# Quarfinder.net
KiCad netlist of a schematic drawn in EAGLE
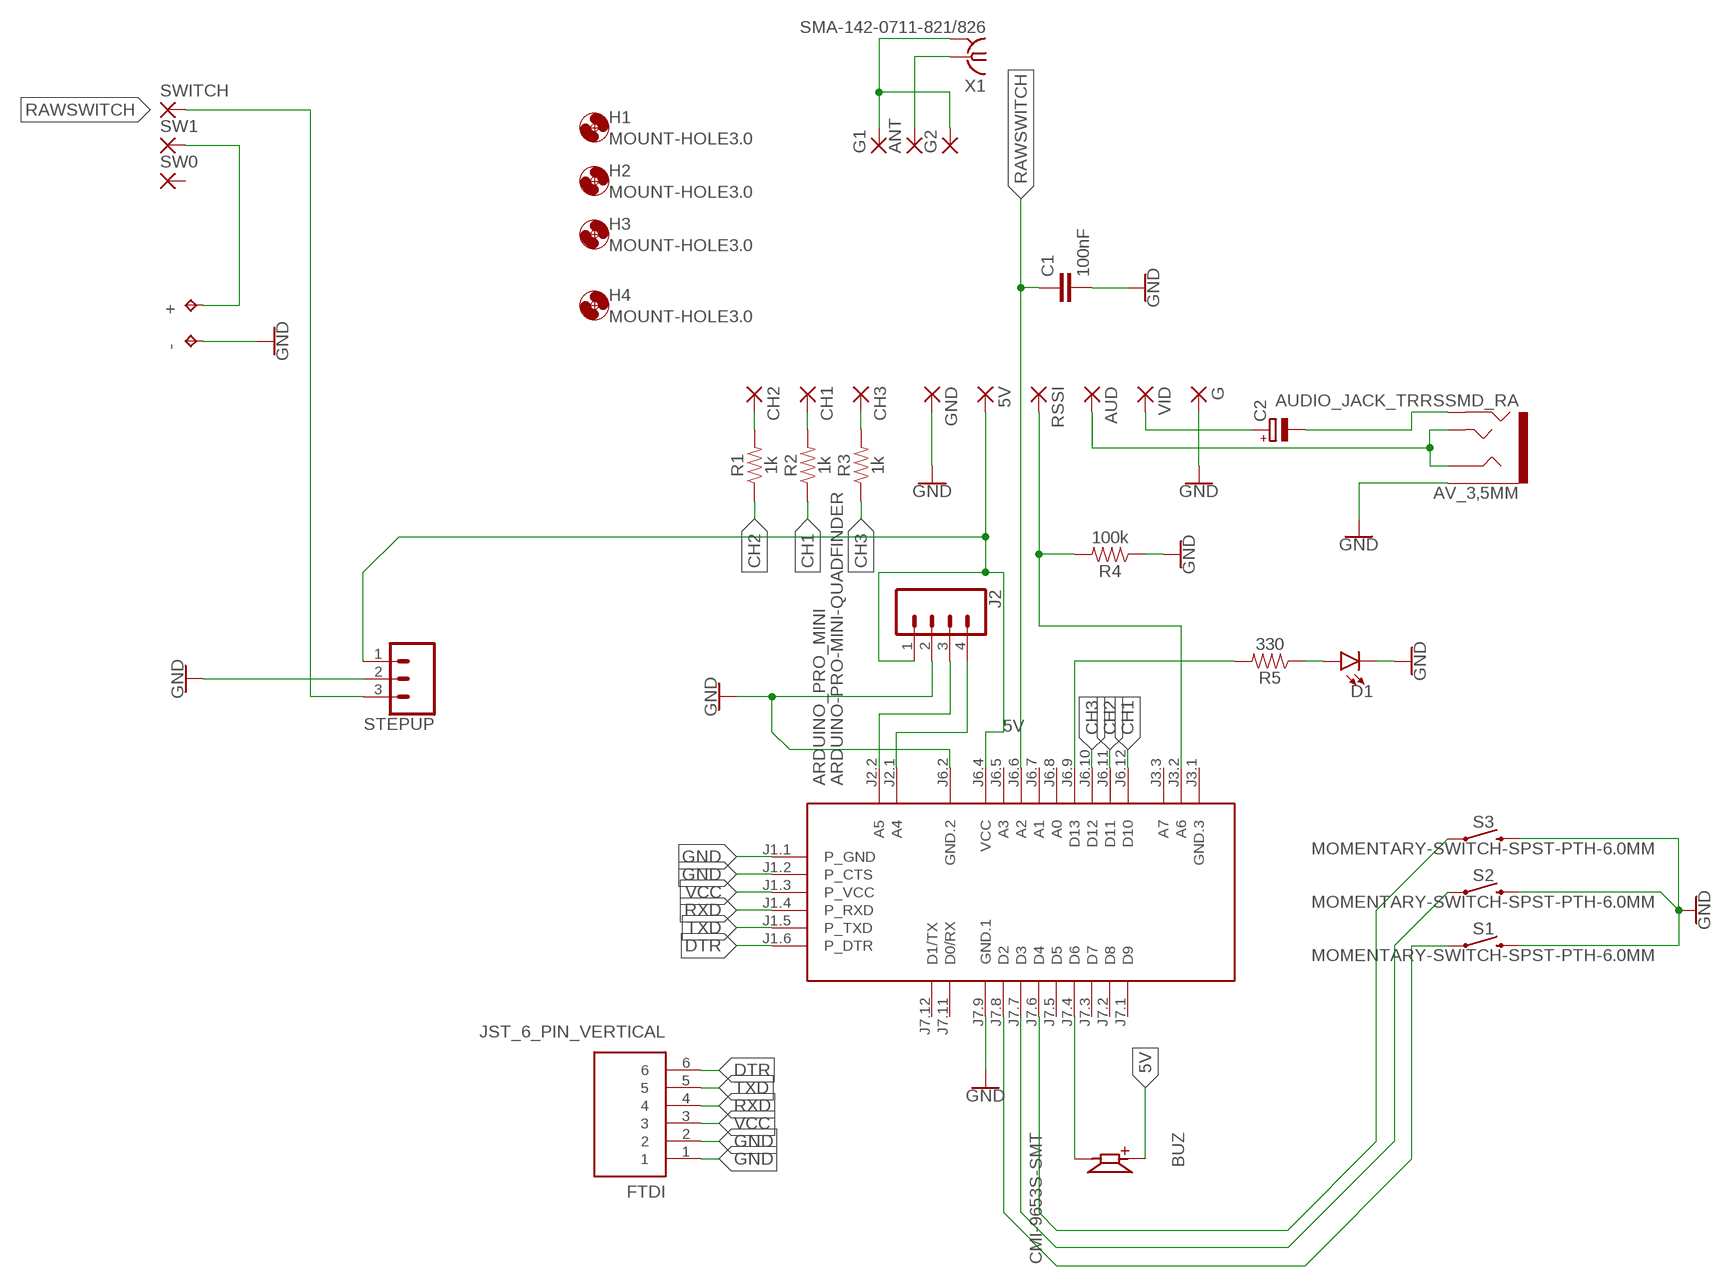
[diagram p0: schematic, sheet 1]

(export (version "E")
  (design (tool "Eeschema 10.0.6"))
  (components
    (comp (ref "+")
      (value "TPTP20R")
      (footprint "eagle-import:TP20R")
      (libsource (lib "eagle-import") (part "TPTP20R"))
    )
    (comp (ref "-")
      (value "TPTP20R")
      (footprint "eagle-import:TP20R")
      (libsource (lib "eagle-import") (part "TPTP20R"))
    )
    (comp (ref "5V")
      (value "SMD2")
      (footprint "eagle-import:SMD1,27-2,54")
      (libsource (lib "eagle-import") (part "SMD2"))
    )
    (comp (ref "ANT")
      (value "SMD2")
      (footprint "eagle-import:SMD1,27-2,54")
      (libsource (lib "eagle-import") (part "SMD2"))
    )
    (comp (ref "ARDUINO_PRO_MINI")
      (value "ARDUINO-PRO-MINI-QUADFINDER")
      (footprint "eagle-import:ARDUINO-PRO-MINI")
      (libsource (lib "eagle-import") (part "ARDUINO-PRO-MINI-QUADFINDER"))
    )
    (comp (ref "AUD")
      (value "SMD2")
      (footprint "eagle-import:SMD1,27-2,54")
      (libsource (lib "eagle-import") (part "SMD2"))
    )
    (comp (ref "AV_3,5MM")
      (value "AUDIO_JACK_TRRSSMD_RA")
      (footprint "eagle-import:AUDIO_JACK_3.5MM_TRRS_SMD_RA")
      (libsource (lib "eagle-import") (part "AUDIO_JACK_TRRSSMD_RA"))
    )
    (comp (ref "BUZ")
      (value "CMI-9653S-SMT")
      (footprint "eagle-import:CUI_CMI-9653S-SMT")
      (fields (field (name "MF") "CUI Inc.") (field (name "MP") "CMI-9653S-SMT-TR"))
      (libsource (lib "eagle-import") (part "CMI-9653S-SMT"))
    )
    (comp (ref "C1")
      (value "100nF")
      (footprint "eagle-import:0603")
      (libsource (lib "eagle-import") (part "1.0UF-0603-16V-10%"))
    )
    (comp (ref "C2")
      (value "CPOL-EUD/7343-31R")
      (footprint "eagle-import:D_7343-31R")
      (libsource (lib "eagle-import") (part "CPOL-EUD/7343-31R"))
    )
    (comp (ref "CH1")
      (value "SMD2")
      (footprint "eagle-import:SMD1,27-2,54")
      (libsource (lib "eagle-import") (part "SMD2"))
    )
    (comp (ref "CH2")
      (value "SMD2")
      (footprint "eagle-import:SMD1,27-2,54")
      (libsource (lib "eagle-import") (part "SMD2"))
    )
    (comp (ref "CH3")
      (value "SMD2")
      (footprint "eagle-import:SMD1,27-2,54")
      (libsource (lib "eagle-import") (part "SMD2"))
    )
    (comp (ref "D1")
      (value "LED3MM")
      (footprint "eagle-import:LED_3MM")
      (libsource (lib "eagle-import") (part "LED3MM"))
    )
    (comp (ref "FTDI")
      (value "JST_6_PIN_VERTICAL")
      (footprint "eagle-import:JST-6-SMD-VERT-1.0MM")
      (libsource (lib "eagle-import") (part "JST_6_PIN_VERTICAL"))
    )
    (comp (ref "G")
      (value "SMD2")
      (footprint "eagle-import:SMD1,27-2,54")
      (libsource (lib "eagle-import") (part "SMD2"))
    )
    (comp (ref "G1")
      (value "SMD2")
      (footprint "eagle-import:SMD1,27-2,54")
      (libsource (lib "eagle-import") (part "SMD2"))
    )
    (comp (ref "G2")
      (value "SMD2")
      (footprint "eagle-import:SMD1,27-2,54")
      (libsource (lib "eagle-import") (part "SMD2"))
    )
    (comp (ref "GND")
      (value "SMD2")
      (footprint "eagle-import:SMD1,27-2,54")
      (libsource (lib "eagle-import") (part "SMD2"))
    )
    (comp (ref "H1")
      (value "MOUNT-HOLE3.0")
      (footprint "eagle-import:3,0")
      (libsource (lib "eagle-import") (part "MOUNT-HOLE3.0"))
    )
    (comp (ref "H2")
      (value "MOUNT-HOLE3.0")
      (footprint "eagle-import:3,0")
      (libsource (lib "eagle-import") (part "MOUNT-HOLE3.0"))
    )
    (comp (ref "H3")
      (value "MOUNT-HOLE3.0")
      (footprint "eagle-import:3,0")
      (libsource (lib "eagle-import") (part "MOUNT-HOLE3.0"))
    )
    (comp (ref "H4")
      (value "MOUNT-HOLE3.0")
      (footprint "eagle-import:3,0")
      (libsource (lib "eagle-import") (part "MOUNT-HOLE3.0"))
    )
    (comp (ref "J2")
      (value "CONN_04")
      (footprint "eagle-import:1X04")
      (libsource (lib "eagle-import") (part "CONN_04"))
    )
    (comp (ref "R1")
      (value "1k")
      (footprint "eagle-import:0603")
      (libsource (lib "eagle-import") (part "1KOHM-0603-1/10W-1%"))
    )
    (comp (ref "R2")
      (value "1k")
      (footprint "eagle-import:0603")
      (libsource (lib "eagle-import") (part "1KOHM-0603-1/10W-1%"))
    )
    (comp (ref "R3")
      (value "1k")
      (footprint "eagle-import:0603")
      (libsource (lib "eagle-import") (part "1KOHM-0603-1/10W-1%"))
    )
    (comp (ref "R4")
      (value "100k")
      (footprint "eagle-import:0603")
      (libsource (lib "eagle-import") (part "1KOHM-0603-1/10W-1%"))
    )
    (comp (ref "R5")
      (value "330")
      (footprint "eagle-import:0603")
      (libsource (lib "eagle-import") (part "1KOHM-0603-1/10W-1%"))
    )
    (comp (ref "RSSI")
      (value "SMD2")
      (footprint "eagle-import:SMD1,27-2,54")
      (libsource (lib "eagle-import") (part "SMD2"))
    )
    (comp (ref "S1")
      (value "MOMENTARY-SWITCH-SPST-PTH-6.0MM")
      (footprint "eagle-import:TACTILE_SWITCH_PTH_6.0MM")
      (libsource (lib "eagle-import") (part "MOMENTARY-SWITCH-SPST-PTH-6.0MM"))
    )
    (comp (ref "S2")
      (value "MOMENTARY-SWITCH-SPST-PTH-6.0MM")
      (footprint "eagle-import:TACTILE_SWITCH_PTH_6.0MM")
      (libsource (lib "eagle-import") (part "MOMENTARY-SWITCH-SPST-PTH-6.0MM"))
    )
    (comp (ref "S3")
      (value "MOMENTARY-SWITCH-SPST-PTH-6.0MM")
      (footprint "eagle-import:TACTILE_SWITCH_PTH_6.0MM")
      (libsource (lib "eagle-import") (part "MOMENTARY-SWITCH-SPST-PTH-6.0MM"))
    )
    (comp (ref "STEPUP")
      (value "CONN_03")
      (footprint "eagle-import:1X03")
      (libsource (lib "eagle-import") (part "CONN_03"))
    )
    (comp (ref "SW0")
      (value "SMD2")
      (footprint "eagle-import:SMD1,27-2,54")
      (libsource (lib "eagle-import") (part "SMD2"))
    )
    (comp (ref "SW1")
      (value "SMD2")
      (footprint "eagle-import:SMD1,27-2,54")
      (libsource (lib "eagle-import") (part "SMD2"))
    )
    (comp (ref "SWITCH")
      (value "SMD2")
      (footprint "eagle-import:SMD1,27-2,54")
      (libsource (lib "eagle-import") (part "SMD2"))
    )
    (comp (ref "VID")
      (value "SMD2")
      (footprint "eagle-import:SMD1,27-2,54")
      (libsource (lib "eagle-import") (part "SMD2"))
    )
    (comp (ref "X1")
      (value "SMA-142-0711-821/826")
      (footprint "eagle-import:J502-ND-142-0711-821_826")
      (fields (field (name "MF") "JOHNSON COMPONENTS") (field (name "MPN") "142-0711-821"))
      (libsource (lib "eagle-import") (part "SMA-142-0711-821/826"))
    )
  )
  (nets
    (net (code "1") (name "5V") (class "Default")
      (node (ref "5V") (pin "1") (pinfunction "P_1") (pintype "passive"))
      (node (ref "ARDUINO_PRO_MINI") (pin "J6.4") (pinfunction "VCC_J6.4") (pintype "power_in"))
      (node (ref "BUZ") (pin "P") (pinfunction "P_P") (pintype "passive"))
      (node (ref "J2") (pin "1") (pinfunction "1_1") (pintype "passive"))
      (node (ref "STEPUP") (pin "1") (pinfunction "1_1") (pintype "passive"))
    )
    (net (code "2") (name "CH1") (class "Default")
      (node (ref "ARDUINO_PRO_MINI") (pin "J6.12") (pinfunction "D10_J6.12") (pintype "bidirectional"))
      (node (ref "R2") (pin "1") (pinfunction "1_1") (pintype "passive"))
    )
    (net (code "3") (name "CH2") (class "Default")
      (node (ref "ARDUINO_PRO_MINI") (pin "J6.11") (pinfunction "D11_J6.11") (pintype "bidirectional"))
      (node (ref "R1") (pin "1") (pinfunction "1_1") (pintype "passive"))
    )
    (net (code "4") (name "CH3") (class "Default")
      (node (ref "ARDUINO_PRO_MINI") (pin "J6.10") (pinfunction "D12_J6.10") (pintype "bidirectional"))
      (node (ref "R3") (pin "1") (pinfunction "1_1") (pintype "passive"))
    )
    (net (code "5") (name "DTR") (class "Default")
      (node (ref "ARDUINO_PRO_MINI") (pin "J1.6") (pinfunction "P_DTR_J1.6") (pintype "bidirectional"))
      (node (ref "FTDI") (pin "6") (pinfunction "6_6") (pintype "bidirectional"))
    )
    (net (code "6") (name "GND") (class "Default")
      (node (ref "-") (pin "TP") (pinfunction "TP_TP") (pintype "input"))
      (node (ref "ARDUINO_PRO_MINI") (pin "J1.1") (pinfunction "P_GND_J1.1") (pintype "bidirectional"))
      (node (ref "ARDUINO_PRO_MINI") (pin "J1.2") (pinfunction "P_CTS_J1.2") (pintype "bidirectional"))
      (node (ref "ARDUINO_PRO_MINI") (pin "J6.2") (pinfunction "GND.2_J6.2") (pintype "power_in"))
      (node (ref "ARDUINO_PRO_MINI") (pin "J7.9") (pinfunction "GND.1_J7.9") (pintype "power_in"))
      (node (ref "AV_3,5MM") (pin "EARTH") (pinfunction "EARTH_EARTH") (pintype "bidirectional"))
      (node (ref "C1") (pin "2") (pinfunction "2_2") (pintype "passive"))
      (node (ref "D1") (pin "K") (pinfunction "C_K") (pintype "passive"))
      (node (ref "FTDI") (pin "1") (pinfunction "1_1") (pintype "bidirectional"))
      (node (ref "FTDI") (pin "2") (pinfunction "2_2") (pintype "bidirectional"))
      (node (ref "G") (pin "1") (pinfunction "P_1") (pintype "passive"))
      (node (ref "G1") (pin "1") (pinfunction "P_1") (pintype "passive"))
      (node (ref "G2") (pin "1") (pinfunction "P_1") (pintype "passive"))
      (node (ref "GND") (pin "1") (pinfunction "P_1") (pintype "passive"))
      (node (ref "J2") (pin "2") (pinfunction "2_2") (pintype "passive"))
      (node (ref "R4") (pin "1") (pinfunction "1_1") (pintype "passive"))
      (node (ref "S1") (pin "3") (pinfunction "2_3") (pintype "passive"))
      (node (ref "S2") (pin "3") (pinfunction "2_3") (pintype "passive"))
      (node (ref "S3") (pin "3") (pinfunction "2_3") (pintype "passive"))
      (node (ref "STEPUP") (pin "2") (pinfunction "2_2") (pintype "passive"))
      (node (ref "X1") (pin "G@1") (pinfunction "2_G@1") (pintype "passive"))
      (node (ref "X1") (pin "G@2") (pinfunction "2_G@2") (pintype "passive"))
      (node (ref "X1") (pin "G@3") (pinfunction "2_G@3") (pintype "passive"))
      (node (ref "X1") (pin "G@4") (pinfunction "2_G@4") (pintype "passive"))
    )
    (net (code "7") (name "Net-(ANT-P)") (class "Default")
      (node (ref "ANT") (pin "1") (pinfunction "P_1") (pintype "passive"))
      (node (ref "X1") (pin "1") (pinfunction "1_1") (pintype "passive"))
    )
    (net (code "8") (name "Net-(ARDUINO_PRO_MINI-A4)") (class "Default")
      (node (ref "ARDUINO_PRO_MINI") (pin "J2.1") (pinfunction "A4_J2.1") (pintype "bidirectional"))
      (node (ref "J2") (pin "4") (pinfunction "4_4") (pintype "passive"))
    )
    (net (code "9") (name "Net-(ARDUINO_PRO_MINI-A5)") (class "Default")
      (node (ref "ARDUINO_PRO_MINI") (pin "J2.2") (pinfunction "A5_J2.2") (pintype "bidirectional"))
      (node (ref "J2") (pin "3") (pinfunction "3_3") (pintype "passive"))
    )
    (net (code "10") (name "Net-(ARDUINO_PRO_MINI-A6)") (class "Default")
      (node (ref "ARDUINO_PRO_MINI") (pin "J3.2") (pinfunction "A6_J3.2") (pintype "bidirectional"))
      (node (ref "R4") (pin "2") (pinfunction "2_2") (pintype "passive"))
      (node (ref "RSSI") (pin "1") (pinfunction "P_1") (pintype "passive"))
    )
    (net (code "11") (name "Net-(ARDUINO_PRO_MINI-D2)") (class "Default")
      (node (ref "ARDUINO_PRO_MINI") (pin "J7.8") (pinfunction "D2_J7.8") (pintype "bidirectional"))
      (node (ref "S1") (pin "1") (pinfunction "1_1") (pintype "passive"))
    )
    (net (code "12") (name "Net-(ARDUINO_PRO_MINI-D3)") (class "Default")
      (node (ref "ARDUINO_PRO_MINI") (pin "J7.7") (pinfunction "D3_J7.7") (pintype "bidirectional"))
      (node (ref "S2") (pin "1") (pinfunction "1_1") (pintype "passive"))
    )
    (net (code "13") (name "Net-(ARDUINO_PRO_MINI-D4)") (class "Default")
      (node (ref "ARDUINO_PRO_MINI") (pin "J7.6") (pinfunction "D4_J7.6") (pintype "bidirectional"))
      (node (ref "S3") (pin "1") (pinfunction "1_1") (pintype "passive"))
    )
    (net (code "14") (name "Net-(ARDUINO_PRO_MINI-D6)") (class "Default")
      (node (ref "ARDUINO_PRO_MINI") (pin "J7.4") (pinfunction "D6_J7.4") (pintype "bidirectional"))
      (node (ref "BUZ") (pin "N") (pinfunction "N_N") (pintype "passive"))
    )
    (net (code "15") (name "Net-(ARDUINO_PRO_MINI-D13)") (class "Default")
      (node (ref "ARDUINO_PRO_MINI") (pin "J6.9") (pinfunction "D13_J6.9") (pintype "bidirectional"))
      (node (ref "R5") (pin "2") (pinfunction "2_2") (pintype "passive"))
    )
    (net (code "16") (name "Net-(AUD-P)") (class "Default")
      (node (ref "AUD") (pin "1") (pinfunction "P_1") (pintype "passive"))
      (node (ref "AV_3,5MM") (pin "RING1") (pinfunction "RING1_RING1") (pintype "bidirectional"))
      (node (ref "AV_3,5MM") (pin "TIP") (pinfunction "TIP_TIP") (pintype "bidirectional"))
    )
    (net (code "17") (name "Net-(AV_3,5MM-PadRING2)") (class "Default")
      (node (ref "AV_3,5MM") (pin "RING2") (pinfunction "RING2_RING2") (pintype "bidirectional"))
      (node (ref "C2") (pin "-") (pinfunction "-_-") (pintype "passive"))
    )
    (net (code "18") (name "Net-(CH1-P)") (class "Default")
      (node (ref "CH1") (pin "1") (pinfunction "P_1") (pintype "passive"))
      (node (ref "R2") (pin "2") (pinfunction "2_2") (pintype "passive"))
    )
    (net (code "19") (name "Net-(CH2-P)") (class "Default")
      (node (ref "CH2") (pin "1") (pinfunction "P_1") (pintype "passive"))
      (node (ref "R1") (pin "2") (pinfunction "2_2") (pintype "passive"))
    )
    (net (code "20") (name "Net-(CH3-P)") (class "Default")
      (node (ref "CH3") (pin "1") (pinfunction "P_1") (pintype "passive"))
      (node (ref "R3") (pin "2") (pinfunction "2_2") (pintype "passive"))
    )
    (net (code "21") (name "Net-(D1-PadA)") (class "Default")
      (node (ref "D1") (pin "A") (pinfunction "A_A") (pintype "passive"))
      (node (ref "R5") (pin "1") (pinfunction "1_1") (pintype "passive"))
    )
    (net (code "22") (name "Net-(SW1-P)") (class "Default")
      (node (ref "+") (pin "TP") (pinfunction "TP_TP") (pintype "input"))
      (node (ref "SW1") (pin "1") (pinfunction "P_1") (pintype "passive"))
    )
    (net (code "23") (name "Net-(VID-P)") (class "Default")
      (node (ref "C2") (pin "+") (pinfunction "+_+") (pintype "passive"))
      (node (ref "VID") (pin "1") (pinfunction "P_1") (pintype "passive"))
    )
    (net (code "24") (name "RAWSWITCH") (class "Default")
      (node (ref "ARDUINO_PRO_MINI") (pin "J6.6") (pinfunction "A2_J6.6") (pintype "bidirectional"))
      (node (ref "C1") (pin "1") (pinfunction "1_1") (pintype "passive"))
      (node (ref "STEPUP") (pin "3") (pinfunction "3_3") (pintype "passive"))
      (node (ref "SWITCH") (pin "1") (pinfunction "P_1") (pintype "passive"))
    )
    (net (code "25") (name "RXD") (class "Default")
      (node (ref "ARDUINO_PRO_MINI") (pin "J1.4") (pinfunction "P_RXD_J1.4") (pintype "bidirectional"))
      (node (ref "FTDI") (pin "4") (pinfunction "4_4") (pintype "bidirectional"))
    )
    (net (code "26") (name "TXD") (class "Default")
      (node (ref "ARDUINO_PRO_MINI") (pin "J1.5") (pinfunction "P_TXD_J1.5") (pintype "bidirectional"))
      (node (ref "FTDI") (pin "5") (pinfunction "5_5") (pintype "bidirectional"))
    )
    (net (code "27") (name "VCC") (class "Default")
      (node (ref "ARDUINO_PRO_MINI") (pin "J1.3") (pinfunction "P_VCC_J1.3") (pintype "bidirectional"))
      (node (ref "FTDI") (pin "3") (pinfunction "3_3") (pintype "bidirectional"))
    )
    (net (code "28") (name "unconnected-(ARDUINO_PRO_MINI-A0-PadJ6.8)") (class "Default")
      (node (ref "ARDUINO_PRO_MINI") (pin "J6.8") (pinfunction "A0_J6.8") (pintype "bidirectional"))
    )
    (net (code "29") (name "unconnected-(ARDUINO_PRO_MINI-A1-PadJ6.7)") (class "Default")
      (node (ref "ARDUINO_PRO_MINI") (pin "J6.7") (pinfunction "A1_J6.7") (pintype "bidirectional"))
    )
    (net (code "30") (name "unconnected-(ARDUINO_PRO_MINI-A3-PadJ6.5)") (class "Default")
      (node (ref "ARDUINO_PRO_MINI") (pin "J6.5") (pinfunction "A3_J6.5") (pintype "bidirectional"))
    )
    (net (code "31") (name "unconnected-(ARDUINO_PRO_MINI-A7-PadJ3.3)") (class "Default")
      (node (ref "ARDUINO_PRO_MINI") (pin "J3.3") (pinfunction "A7_J3.3") (pintype "bidirectional"))
    )
    (net (code "32") (name "unconnected-(ARDUINO_PRO_MINI-D0{slash}RX-PadJ7.11)") (class "Default")
      (node (ref "ARDUINO_PRO_MINI") (pin "J7.11") (pinfunction "D0/RX_J7.11") (pintype "bidirectional"))
    )
    (net (code "33") (name "unconnected-(ARDUINO_PRO_MINI-D1{slash}TX-PadJ7.12)") (class "Default")
      (node (ref "ARDUINO_PRO_MINI") (pin "J7.12") (pinfunction "D1/TX_J7.12") (pintype "bidirectional"))
    )
    (net (code "34") (name "unconnected-(ARDUINO_PRO_MINI-D5-PadJ7.5)") (class "Default")
      (node (ref "ARDUINO_PRO_MINI") (pin "J7.5") (pinfunction "D5_J7.5") (pintype "bidirectional"))
    )
    (net (code "35") (name "unconnected-(ARDUINO_PRO_MINI-D7-PadJ7.3)") (class "Default")
      (node (ref "ARDUINO_PRO_MINI") (pin "J7.3") (pinfunction "D7_J7.3") (pintype "bidirectional"))
    )
    (net (code "36") (name "unconnected-(ARDUINO_PRO_MINI-D8-PadJ7.2)") (class "Default")
      (node (ref "ARDUINO_PRO_MINI") (pin "J7.2") (pinfunction "D8_J7.2") (pintype "bidirectional"))
    )
    (net (code "37") (name "unconnected-(ARDUINO_PRO_MINI-D9-PadJ7.1)") (class "Default")
      (node (ref "ARDUINO_PRO_MINI") (pin "J7.1") (pinfunction "D9_J7.1") (pintype "bidirectional"))
    )
    (net (code "38") (name "unconnected-(ARDUINO_PRO_MINI-GND.3-PadJ3.1)") (class "Default")
      (node (ref "ARDUINO_PRO_MINI") (pin "J3.1") (pinfunction "GND.3_J3.1") (pintype "bidirectional"))
    )
    (net (code "39") (name "unconnected-(SW0-P-Pad1)") (class "Default")
      (node (ref "SW0") (pin "1") (pinfunction "P_1") (pintype "passive"))
    )
  )
)
